# COMMUNICATION.net
KiCad netlist of a schematic drawn in Altium Designer
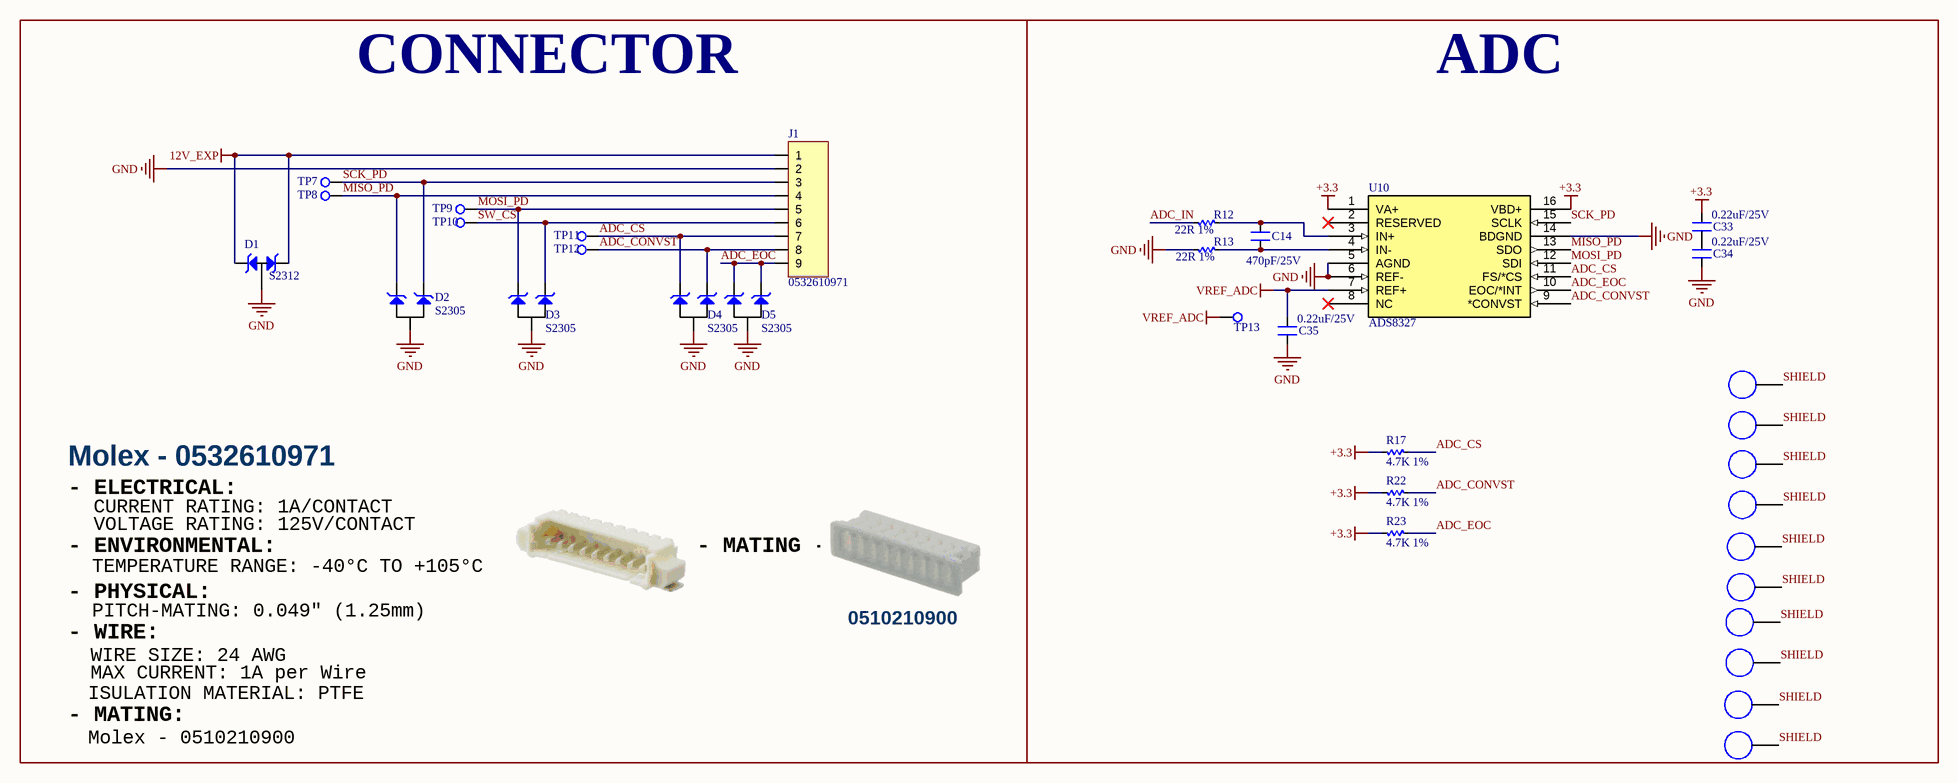
[diagram p0: COMMUNICATION.SchDoc]

(export (version "E")
  (design (tool "Eeschema 10.0.6"))
  (components
    (comp (ref "C14")
      (value "470pF/25V")
      (footprint "CN-SMD-0603")
      (description "0603")
      (libsource (lib "Capacitors") (part "CM"))
    )
    (comp (ref "C33")
      (value "0.22uF/25V")
      (footprint "CN-SMD-0603")
      (description "0603")
      (libsource (lib "Capacitors") (part "CM"))
    )
    (comp (ref "C34")
      (value "0.22uF/25V")
      (footprint "CN-SMD-0603")
      (description "0603")
      (libsource (lib "Capacitors") (part "CM"))
    )
    (comp (ref "C35")
      (value "0.22uF/25V")
      (footprint "CN-SMD-0603")
      (description "0603")
      (libsource (lib "Capacitors") (part "CM"))
    )
    (comp (ref "D1")
      (value "S2312")
      (footprint "SOT23-123")
      (description "TVS DIODE 12VWM 19VC SOT23, P/N:  S2312")
      (libsource (lib "Library") (part "S2315"))
    )
    (comp (ref "D2")
      (value "S2305")
      (footprint "SOT23-123")
      (description "TVS DIODE 5VWM 10.8VC SOT23, P/N:  \r\nS2305")
      (libsource (lib "Library") (part "S2303"))
    )
    (comp (ref "D3")
      (value "S2305")
      (footprint "SOT23-123")
      (description "TVS DIODE 5VWM 10.8VC SOT23, P/N:  \r\nS2305")
      (libsource (lib "Library") (part "S2303"))
    )
    (comp (ref "D4")
      (value "S2305")
      (footprint "SOT23-123")
      (description "TVS DIODE 5VWM 10.8VC SOT23, P/N:  \r\nS2305")
      (libsource (lib "Library") (part "S2303"))
    )
    (comp (ref "D5")
      (value "S2305")
      (footprint "SOT23-123")
      (description "TVS DIODE 5VWM 10.8VC SOT23, P/N:  \r\nS2305")
      (libsource (lib "Library") (part "S2303"))
    )
    (comp (ref "H1") (value "HOLD") (footprint "M3 - 6mm") (libsource (lib "Library_HUNG") (part "PAD_HOLD")))
    (comp (ref "H2") (value "HOLD") (footprint "M3 - 6mm") (libsource (lib "Library_HUNG") (part "PAD_HOLD")))
    (comp (ref "H3") (value "HOLD") (footprint "M3 - 6mm") (libsource (lib "Library_HUNG") (part "PAD_HOLD")))
    (comp (ref "H4") (value "HOLD") (footprint "M3 - 6mm") (libsource (lib "Library_HUNG") (part "PAD_HOLD")))
    (comp (ref "H5") (value "HOLD") (footprint "M3 - 6mm") (libsource (lib "Library_HUNG") (part "PAD_HOLD")))
    (comp (ref "H6") (value "HOLD") (footprint "M3 - 6mm") (libsource (lib "Library_HUNG") (part "PAD_HOLD")))
    (comp (ref "H7") (value "HOLD") (footprint "M3 - 6mm") (libsource (lib "Library_HUNG") (part "PAD_HOLD")))
    (comp (ref "H8") (value "HOLD") (footprint "M3 - 6mm") (libsource (lib "Library_HUNG") (part "PAD_HOLD")))
    (comp (ref "H9") (value "HOLD") (footprint "M3 - 6mm") (libsource (lib "Library_HUNG") (part "PAD_HOLD")))
    (comp (ref "H10")
      (value "HOLD")
      (footprint "M3 - 6mm")
      (libsource (lib "Library_HUNG") (part "PAD_HOLD"))
    )
    (comp (ref "J1")
      (value "0532610971")
      (footprint "0532610971")
      (description "WR-PHD 2.54 mm Angled Socket Header")
      (fields
        (field (name "MANUFACTURER") "Würth Elektronik eiSos GmbH")
        (field (name "PARTNO") "613009143121")
        (field (name "CREATED BY") "Karrer Zheng")
      )
      (libsource (lib "Library") (part "JP9"))
    )
    (comp (ref "R12")
      (value "22R 1%")
      (footprint "RES-SMD-0603")
      (description "0603")
      (fields
        (field (name "MANUFACTURER") "Generic Components")
        (field (name "PUBLISHER") "Altium Hobart Technology Centre")
      )
      (libsource (lib "Library") (part "Res-SMD"))
    )
    (comp (ref "R13")
      (value "22R 1%")
      (footprint "RES-SMD-0603")
      (description "0603")
      (fields
        (field (name "MANUFACTURER") "Generic Components")
        (field (name "PUBLISHER") "Altium Hobart Technology Centre")
      )
      (libsource (lib "Library") (part "Res-SMD"))
    )
    (comp (ref "R17")
      (value "4.7K 1%")
      (footprint "RES-SMD-0603")
      (description "0603")
      (fields
        (field (name "MANUFACTURER") "Generic Components")
        (field (name "PUBLISHER") "Altium Hobart Technology Centre")
      )
      (libsource (lib "Library") (part "Res-SMD"))
    )
    (comp (ref "R22")
      (value "4.7K 1%")
      (footprint "RES-SMD-0603")
      (description "0603")
      (fields
        (field (name "MANUFACTURER") "Generic Components")
        (field (name "PUBLISHER") "Altium Hobart Technology Centre")
      )
      (libsource (lib "Library") (part "Res-SMD"))
    )
    (comp (ref "R23")
      (value "4.7K 1%")
      (footprint "RES-SMD-0603")
      (description "0603")
      (fields
        (field (name "MANUFACTURER") "Generic Components")
        (field (name "PUBLISHER") "Altium Hobart Technology Centre")
      )
      (libsource (lib "Library") (part "Res-SMD"))
    )
    (comp (ref "TP7")
      (value "Test_Point")
      (footprint "TESTPOINT")
      (libsource (lib "Library_HUNG") (part "Test_Point"))
    )
    (comp (ref "TP8")
      (value "Test_Point")
      (footprint "TESTPOINT")
      (libsource (lib "Library_HUNG") (part "Test_Point"))
    )
    (comp (ref "TP9")
      (value "Test_Point")
      (footprint "TESTPOINT")
      (libsource (lib "Library_HUNG") (part "Test_Point"))
    )
    (comp (ref "TP10")
      (value "Test_Point")
      (footprint "TESTPOINT")
      (libsource (lib "Library_HUNG") (part "Test_Point"))
    )
    (comp (ref "TP11")
      (value "Test_Point")
      (footprint "TESTPOINT")
      (libsource (lib "Library_HUNG") (part "Test_Point"))
    )
    (comp (ref "TP12")
      (value "Test_Point")
      (footprint "TESTPOINT")
      (libsource (lib "Library_HUNG") (part "Test_Point"))
    )
    (comp (ref "TP13")
      (value "Test_Point")
      (footprint "TESTPOINT")
      (libsource (lib "Library_HUNG") (part "Test_Point"))
    )
    (comp (ref "U10")
      (value "ADS8327")
      (footprint "TSSOP16")
      (description "IC ADC 16BIT SAR 16TSSOP")
      (libsource (lib "Library") (part "ADS8327"))
    )
  )
  (nets
    (net (code "1") (name "+3.3") (class "Default")
      (node (ref "C33") (pin "2") (pinfunction "2_2") (pintype "passive"))
      (node (ref "R17") (pin "2") (pinfunction "2_2") (pintype "passive"))
      (node (ref "R22") (pin "2") (pinfunction "2_2") (pintype "passive"))
      (node (ref "R23") (pin "2") (pinfunction "2_2") (pintype "passive"))
      (node (ref "U10") (pin "1") (pinfunction "VA+_1") (pintype "power_in"))
      (node (ref "U10") (pin "16") (pinfunction "VBD+_16") (pintype "power_in"))
    )
    (net (code "2") (name "/ADC_CONVST") (class "Default")
      (node (ref "D4") (pin "3") (pintype "passive"))
      (node (ref "J1") (pin "8") (pinfunction "8_8") (pintype "passive"))
      (node (ref "R22") (pin "1") (pinfunction "1_1") (pintype "passive"))
      (node (ref "TP12") (pin "1") (pintype "power_in"))
      (node (ref "U10") (pin "9") (pinfunction "*CONVST_9") (pintype "input"))
    )
    (net (code "3") (name "/ADC_CS") (class "Default")
      (node (ref "D4") (pin "1") (pintype "passive"))
      (node (ref "J1") (pin "7") (pinfunction "7_7") (pintype "passive"))
      (node (ref "R17") (pin "1") (pinfunction "1_1") (pintype "passive"))
      (node (ref "TP11") (pin "1") (pintype "power_in"))
      (node (ref "U10") (pin "11") (pinfunction "FS/*CS_11") (pintype "input"))
    )
    (net (code "4") (name "/ADC_EOC") (class "Default")
      (node (ref "D5") (pin "1") (pintype "passive"))
      (node (ref "D5") (pin "3") (pintype "passive"))
      (node (ref "J1") (pin "9") (pinfunction "9_9") (pintype "passive"))
      (node (ref "R23") (pin "1") (pinfunction "1_1") (pintype "passive"))
      (node (ref "U10") (pin "10") (pinfunction "EOC/*INT_10") (pintype "output"))
    )
    (net (code "5") (name "/ADC_IN") (class "Default")
      (node (ref "R12") (pin "2") (pinfunction "2_2") (pintype "passive"))
    )
    (net (code "6") (name "/MISO_PD") (class "Default")
      (node (ref "D2") (pin "3") (pintype "passive"))
      (node (ref "J1") (pin "4") (pinfunction "4_4") (pintype "passive"))
      (node (ref "TP8") (pin "1") (pintype "power_in"))
      (node (ref "U10") (pin "13") (pinfunction "SDO_13") (pintype "output"))
    )
    (net (code "7") (name "/MOSI_PD") (class "Default")
      (node (ref "D3") (pin "1") (pintype "passive"))
      (node (ref "J1") (pin "5") (pinfunction "5_5") (pintype "passive"))
      (node (ref "TP9") (pin "1") (pintype "power_in"))
      (node (ref "U10") (pin "12") (pinfunction "SDI_12") (pintype "input"))
    )
    (net (code "8") (name "/SCK_PD") (class "Default")
      (node (ref "D2") (pin "1") (pintype "passive"))
      (node (ref "J1") (pin "3") (pinfunction "3_3") (pintype "passive"))
      (node (ref "TP7") (pin "1") (pintype "power_in"))
      (node (ref "U10") (pin "15") (pinfunction "SCLK_15") (pintype "input"))
    )
    (net (code "9") (name "/SHIELD") (class "Default")
      (node (ref "H1") (pin "1") (pintype "power_in"))
      (node (ref "H10") (pin "1") (pintype "power_in"))
      (node (ref "H2") (pin "1") (pintype "power_in"))
      (node (ref "H3") (pin "1") (pintype "power_in"))
      (node (ref "H4") (pin "1") (pintype "power_in"))
      (node (ref "H5") (pin "1") (pintype "power_in"))
      (node (ref "H6") (pin "1") (pintype "power_in"))
      (node (ref "H7") (pin "1") (pintype "power_in"))
      (node (ref "H8") (pin "1") (pintype "power_in"))
      (node (ref "H9") (pin "1") (pintype "power_in"))
    )
    (net (code "10") (name "/SW_CS") (class "Default")
      (node (ref "D3") (pin "3") (pintype "passive"))
      (node (ref "J1") (pin "6") (pinfunction "6_6") (pintype "passive"))
      (node (ref "TP10") (pin "1") (pintype "power_in"))
    )
    (net (code "11") (name "12V_EXP") (class "Default")
      (node (ref "D1") (pin "1") (pintype "passive"))
      (node (ref "D1") (pin "3") (pintype "passive"))
      (node (ref "J1") (pin "1") (pinfunction "1_1") (pintype "passive"))
    )
    (net (code "12") (name "GND") (class "Default")
      (node (ref "C34") (pin "1") (pinfunction "1_1") (pintype "passive"))
      (node (ref "C35") (pin "1") (pinfunction "1_1") (pintype "passive"))
      (node (ref "D1") (pin "2") (pintype "passive"))
      (node (ref "D2") (pin "2") (pintype "passive"))
      (node (ref "D3") (pin "2") (pintype "passive"))
      (node (ref "D4") (pin "2") (pintype "passive"))
      (node (ref "D5") (pin "2") (pintype "passive"))
      (node (ref "J1") (pin "2") (pinfunction "2_2") (pintype "passive"))
      (node (ref "R13") (pin "2") (pinfunction "2_2") (pintype "passive"))
      (node (ref "U10") (pin "14") (pinfunction "BDGND_14") (pintype "power_in"))
      (node (ref "U10") (pin "5") (pinfunction "AGND_5") (pintype "power_in"))
      (node (ref "U10") (pin "6") (pinfunction "REF-_6") (pintype "input"))
    )
    (net (code "13") (name "Net-(C33-Pad1)") (class "Default")
      (node (ref "C33") (pin "1") (pinfunction "1_1") (pintype "passive"))
      (node (ref "C34") (pin "2") (pinfunction "2_2") (pintype "passive"))
    )
    (net (code "14") (name "Net-(U10-IN+)") (class "Default")
      (node (ref "C14") (pin "2") (pinfunction "2_2") (pintype "passive"))
      (node (ref "R12") (pin "1") (pinfunction "1_1") (pintype "passive"))
      (node (ref "U10") (pin "3") (pinfunction "IN+_3") (pintype "input"))
    )
    (net (code "15") (name "Net-(U10-IN-)") (class "Default")
      (node (ref "C14") (pin "1") (pinfunction "1_1") (pintype "passive"))
      (node (ref "R13") (pin "1") (pinfunction "1_1") (pintype "passive"))
      (node (ref "U10") (pin "4") (pinfunction "IN-_4") (pintype "input"))
    )
    (net (code "16") (name "VREF_ADC") (class "Default")
      (node (ref "C35") (pin "2") (pinfunction "2_2") (pintype "passive"))
      (node (ref "TP13") (pin "1") (pintype "power_in"))
      (node (ref "U10") (pin "7") (pinfunction "REF+_7") (pintype "input"))
    )
    (net (code "17") (name "unconnected-(U10-NC-Pad8)") (class "Default")
      (node (ref "U10") (pin "8") (pinfunction "NC_8") (pintype "passive+no_connect"))
    )
    (net (code "18") (name "unconnected-(U10-RESERVED-Pad2)") (class "Default")
      (node (ref "U10") (pin "2") (pinfunction "RESERVED_2") (pintype "passive+no_connect"))
    )
  )
)
